# PCB_ALIM_version_5.net
KiCad netlist of a schematic drawn in EAGLE
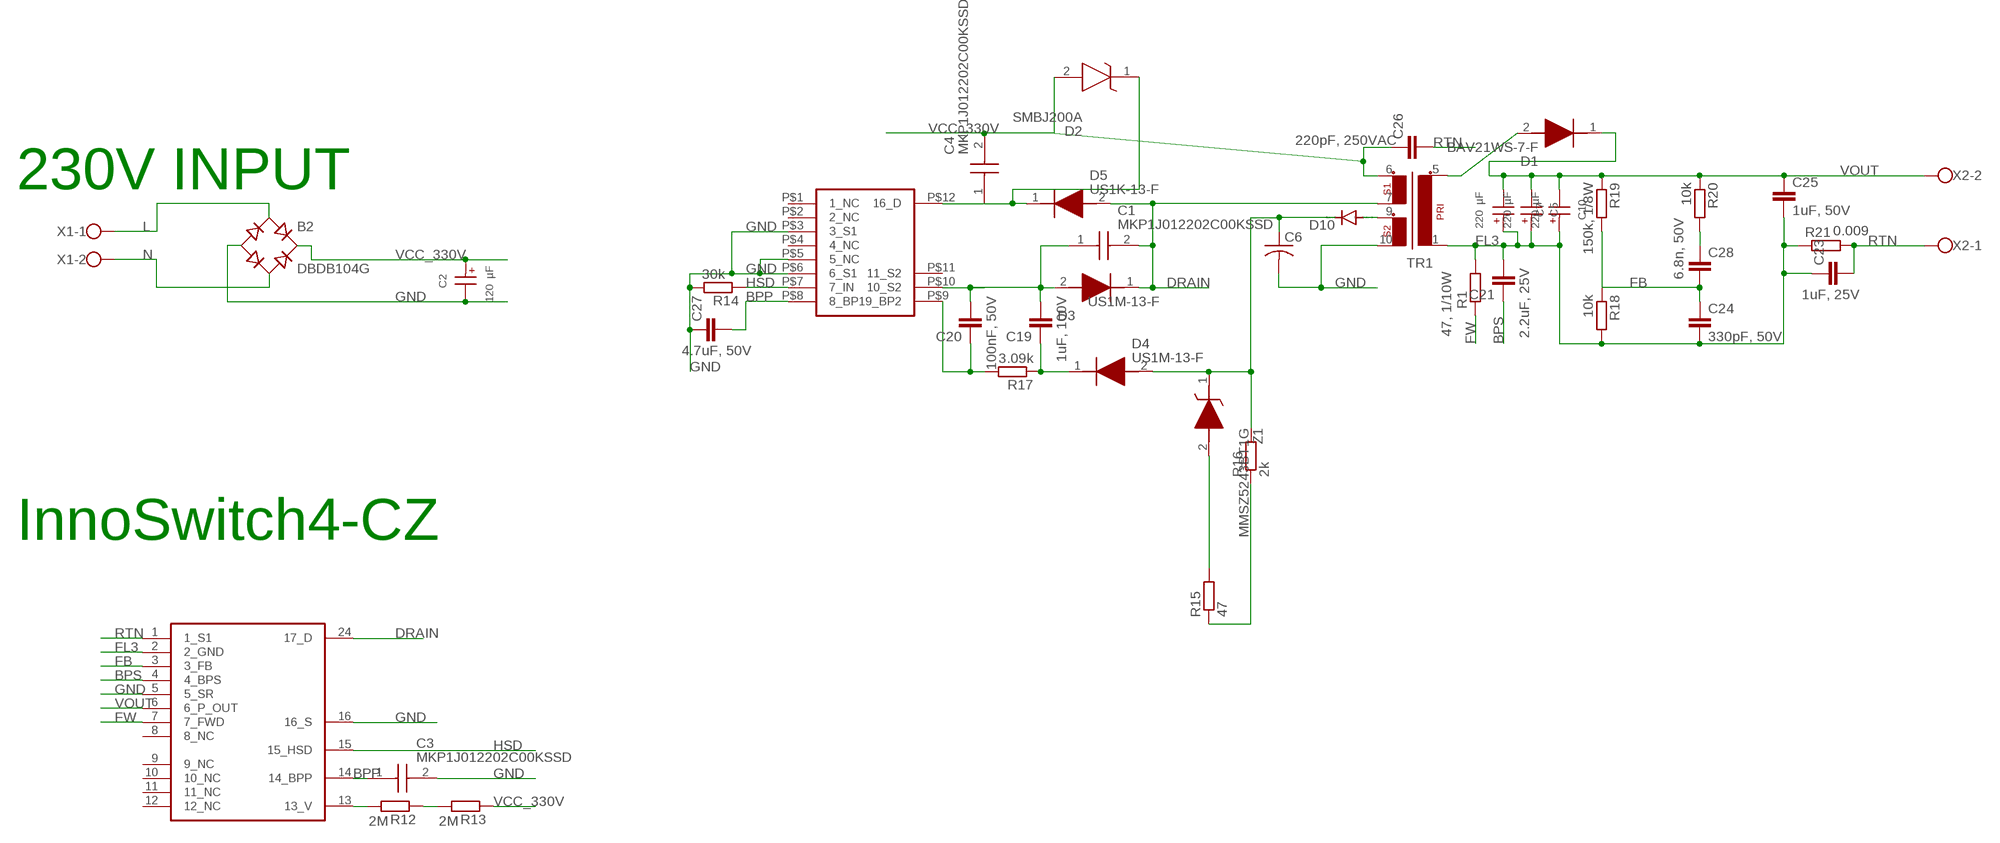
[diagram p0: schematic, sheet 1]

(export (version "E")
  (design (tool "Eeschema 10.0.6"))
  (components
    (comp (ref "B2")
      (value "DBDB104G")
      (footprint "eagle-import:DB")
      (libsource (lib "eagle-import") (part "DB?GDB104"))
    )
    (comp (ref "C1")
      (value "MKP1J012202C00KSSD")
      (footprint "eagle-import:MKP1J012202C00KSSD")
      (fields (field (name "MOUSER_PART_NUMBER") "505-M102200/630/10"))
      (libsource (lib "eagle-import") (part "MKP1J012202C00KSSD"))
    )
    (comp (ref "C2")
      (value "120 µF")
      (footprint "eagle-import:WCAP-ATG8_18X41X7.5(DXL)")
      (libsource (lib "eagle-import") (part "WCAP-ATG8_18X41_860011381013"))
    )
    (comp (ref "C3")
      (value "MKP1J012202C00KSSD")
      (footprint "eagle-import:MKP1J012202C00KSSD")
      (fields (field (name "MOUSER_PART_NUMBER") "505-M102200/630/10"))
      (libsource (lib "eagle-import") (part "MKP1J012202C00KSSD"))
    )
    (comp (ref "C4")
      (value "MKP1J012202C00KSSD")
      (footprint "eagle-import:MKP1J012202C00KSSD")
      (fields (field (name "MOUSER_PART_NUMBER") "505-M102200/630/10"))
      (libsource (lib "eagle-import") (part "MKP1J012202C00KSSD"))
    )
    (comp (ref "C5")
      (value "220 µF")
      (footprint "eagle-import:WCAP-ASLI_10X10.5(DXL)")
      (libsource (lib "eagle-import") (part "WCAP-ASLI_10X10.5_865080657018"))
    )
    (comp (ref "C6")
      (value "C-US050H075X075")
      (footprint "eagle-import:C050H075X075")
      (libsource (lib "eagle-import") (part "C-US050H075X075"))
    )
    (comp (ref "C7")
      (value "220 µF")
      (footprint "eagle-import:WCAP-ASLI_10X10.5(DXL)")
      (libsource (lib "eagle-import") (part "WCAP-ASLI_10X10.5_865080657018"))
    )
    (comp (ref "C10")
      (value "220 µF")
      (footprint "eagle-import:WCAP-ASLI_10X10.5(DXL)")
      (libsource (lib "eagle-import") (part "WCAP-ASLI_10X10.5_865080657018"))
    )
    (comp (ref "C19")
      (value "1uF, 100V")
      (footprint "eagle-import:C0603")
      (libsource (lib "eagle-import") (part "C-EUC0603"))
    )
    (comp (ref "C20")
      (value "100nF, 50V")
      (footprint "eagle-import:C0603")
      (libsource (lib "eagle-import") (part "C-EUC0603"))
    )
    (comp (ref "C21")
      (value "2.2uF, 25V")
      (footprint "eagle-import:C0603")
      (libsource (lib "eagle-import") (part "C-EUC0603"))
    )
    (comp (ref "C23")
      (value "1uF, 25V")
      (footprint "eagle-import:C0603")
      (libsource (lib "eagle-import") (part "C-EUC0603"))
    )
    (comp (ref "C24")
      (value "330pF, 50V")
      (footprint "eagle-import:C0603")
      (libsource (lib "eagle-import") (part "C-EUC0603"))
    )
    (comp (ref "C25")
      (value "1uF, 50V")
      (footprint "eagle-import:C0603")
      (libsource (lib "eagle-import") (part "C-EUC0603"))
    )
    (comp (ref "C26")
      (value "220pF, 250VAC")
      (footprint "eagle-import:C0603")
      (libsource (lib "eagle-import") (part "C-EUC0603"))
    )
    (comp (ref "C27")
      (value "4.7uF, 50V")
      (footprint "eagle-import:C0603")
      (libsource (lib "eagle-import") (part "C-EUC0603"))
    )
    (comp (ref "C28")
      (value "6.8n, 50V")
      (footprint "eagle-import:C0603")
      (libsource (lib "eagle-import") (part "C-EUC0603"))
    )
    (comp (ref "D1")
      (value "BAV21WS-7-F")
      (footprint "eagle-import:SOD2513X120N")
      (fields (field (name "MOUSER_PART_NUMBER") "621-BAV21WS-F"))
      (libsource (lib "eagle-import") (part "BAV21WS-7-F"))
    )
    (comp (ref "D2")
      (value "SMBJ200A")
      (footprint "eagle-import:DIOM5436X261N")
      (fields (field (name "MOUSER_PART_NUMBER") "576-SMBJ200A"))
      (libsource (lib "eagle-import") (part "SMBJ200A"))
    )
    (comp (ref "D3")
      (value "US1M-13-F")
      (footprint "eagle-import:SODFL5226X240N")
      (fields (field (name "MOUSER_PART_NUMBER") "621-US1M-F"))
      (libsource (lib "eagle-import") (part "US1M-13-F"))
    )
    (comp (ref "D4")
      (value "US1M-13-F")
      (footprint "eagle-import:SODFL5226X240N")
      (fields (field (name "MOUSER_PART_NUMBER") "621-US1M-F"))
      (libsource (lib "eagle-import") (part "US1M-13-F"))
    )
    (comp (ref "D5")
      (value "US1K-13-F")
      (footprint "eagle-import:DIOM5226X240N")
      (fields (field (name "MOUSER_PART_NUMBER") "621-US1K-F"))
      (libsource (lib "eagle-import") (part "US1K-13-F"))
    )
    (comp (ref "D10")
      (value "1N4933")
      (footprint "eagle-import:DO41-10")
      (libsource (lib "eagle-import") (part "1N4933"))
    )
    (comp (ref "R1")
      (value "47, 1/10W")
      (footprint "eagle-import:R0603")
      (libsource (lib "eagle-import") (part "R-EU_R0603"))
    )
    (comp (ref "R12")
      (value "2M")
      (footprint "eagle-import:R0603")
      (libsource (lib "eagle-import") (part "R-EU_R0603"))
    )
    (comp (ref "R13")
      (value "2M")
      (footprint "eagle-import:R0603")
      (libsource (lib "eagle-import") (part "R-EU_R0603"))
    )
    (comp (ref "R14")
      (value "30k")
      (footprint "eagle-import:R0603")
      (libsource (lib "eagle-import") (part "R-EU_R0603"))
    )
    (comp (ref "R15")
      (value "47")
      (footprint "eagle-import:R0603")
      (libsource (lib "eagle-import") (part "R-EU_R0603"))
    )
    (comp (ref "R16")
      (value "2k")
      (footprint "eagle-import:R0603")
      (libsource (lib "eagle-import") (part "R-EU_R0603"))
    )
    (comp (ref "R17")
      (value "3.09k")
      (footprint "eagle-import:R0603")
      (libsource (lib "eagle-import") (part "R-EU_R0603"))
    )
    (comp (ref "R18")
      (value "10k")
      (footprint "eagle-import:R0603")
      (libsource (lib "eagle-import") (part "R-EU_R0603"))
    )
    (comp (ref "R19")
      (value "150k, 1/8W")
      (footprint "eagle-import:R0603")
      (libsource (lib "eagle-import") (part "R-EU_R0603"))
    )
    (comp (ref "R20")
      (value "10k")
      (footprint "eagle-import:R0603")
      (libsource (lib "eagle-import") (part "R-EU_R0603"))
    )
    (comp (ref "R21")
      (value "0.009")
      (footprint "eagle-import:R0603")
      (libsource (lib "eagle-import") (part "R-EU_R0603"))
    )
    (comp (ref "TR1")
      (value "EI30-2")
      (footprint "eagle-import:EI30-2")
      (libsource (lib "eagle-import") (part "EI30-2"))
    )
    (comp (ref "U$1")
      (value "INNOSWITCH4_DEVICE")
      (footprint "eagle-import:INNOSWITCH4_FOOTPRINT")
      (libsource (lib "eagle-import") (part "INNOSWITCH4_DEVICE"))
    )
    (comp (ref "U$2")
      (value "CPZ1061M_DEVICE")
      (footprint "eagle-import:CPZ1061M_FOOTPRINT")
      (libsource (lib "eagle-import") (part "CPZ1061M_DEVICE"))
    )
    (comp (ref "X1")
      (value "W237-102")
      (footprint "eagle-import:W237-102")
      (fields (field (name "MPN") "237-102"))
      (libsource (lib "eagle-import") (part "W237-102"))
    )
    (comp (ref "X2")
      (value "W237-102")
      (footprint "eagle-import:W237-102")
      (fields (field (name "MPN") "237-102"))
      (libsource (lib "eagle-import") (part "W237-102"))
    )
    (comp (ref "Z1")
      (value "MMSZ5243BT1G")
      (footprint "eagle-import:SOD3716X135N")
      (fields (field (name "MOUSER_PART_NUMBER") "863-MMSZ5243BT1G"))
      (libsource (lib "eagle-import") (part "MMSZ5243BT1G"))
    )
  )
  (nets
    (net (code "1") (name "/BPP") (class "Default")
      (node (ref "C27") (pin "2") (pinfunction "2_2") (pintype "passive"))
      (node (ref "C3") (pin "1") (pinfunction "1_1") (pintype "bidirectional"))
      (node (ref "U$1") (pin "14") (pinfunction "14_BPP_14") (pintype "output"))
      (node (ref "U$2") (pin "P$8") (pinfunction "8_BP1_P$8") (pintype "input"))
    )
    (net (code "2") (name "/BPS") (class "Default")
      (node (ref "C21") (pin "1") (pinfunction "1_1") (pintype "passive"))
      (node (ref "U$1") (pin "4") (pinfunction "4_BPS_4") (pintype "input"))
    )
    (net (code "3") (name "/DRAIN") (class "Default")
      (node (ref "C1") (pin "2") (pinfunction "2_2") (pintype "bidirectional"))
      (node (ref "D3") (pin "1") (pinfunction "K_1") (pintype "bidirectional"))
      (node (ref "D5") (pin "2") (pinfunction "A_2") (pintype "bidirectional"))
      (node (ref "TR1") (pin "7") (pinfunction "4_7") (pintype "passive"))
      (node (ref "U$1") (pin "24") (pinfunction "17_D_24") (pintype "output"))
    )
    (net (code "4") (name "/FB") (class "Default")
      (node (ref "C24") (pin "1") (pinfunction "1_1") (pintype "passive"))
      (node (ref "C28") (pin "2") (pinfunction "2_2") (pintype "passive"))
      (node (ref "R18") (pin "1") (pinfunction "1_1") (pintype "passive"))
      (node (ref "R19") (pin "2") (pinfunction "2_2") (pintype "passive"))
      (node (ref "U$1") (pin "3") (pinfunction "3_FB_3") (pintype "input"))
    )
    (net (code "5") (name "/FL3") (class "Default")
      (node (ref "C10") (pin "1") (pinfunction "+_1") (pintype "passive"))
      (node (ref "C21") (pin "2") (pinfunction "2_2") (pintype "passive"))
      (node (ref "C23") (pin "1") (pinfunction "1_1") (pintype "passive"))
      (node (ref "C24") (pin "2") (pinfunction "2_2") (pintype "passive"))
      (node (ref "C25") (pin "2") (pinfunction "2_2") (pintype "passive"))
      (node (ref "C5") (pin "1") (pinfunction "+_1") (pintype "passive"))
      (node (ref "C7") (pin "1") (pinfunction "+_1") (pintype "passive"))
      (node (ref "R1") (pin "2") (pinfunction "2_2") (pintype "passive"))
      (node (ref "R18") (pin "2") (pinfunction "2_2") (pintype "passive"))
      (node (ref "R21") (pin "1") (pinfunction "1_1") (pintype "passive"))
      (node (ref "TR1") (pin "1") (pinfunction "1_1") (pintype "passive"))
      (node (ref "U$1") (pin "2") (pinfunction "2_GND_2") (pintype "input"))
    )
    (net (code "6") (name "/FW") (class "Default")
      (node (ref "R1") (pin "1") (pinfunction "1_1") (pintype "passive"))
      (node (ref "U$1") (pin "7") (pinfunction "7_FWD_7") (pintype "input"))
    )
    (net (code "7") (name "/GND") (class "Default")
      (node (ref "B2") (pin "-") (pinfunction "-_-") (pintype "passive"))
      (node (ref "C2") (pin "2") (pinfunction "-_2") (pintype "passive"))
      (node (ref "C27") (pin "1") (pinfunction "1_1") (pintype "passive"))
      (node (ref "C3") (pin "2") (pinfunction "2_2") (pintype "bidirectional"))
      (node (ref "C6") (pin "2") (pinfunction "2_2") (pintype "passive"))
      (node (ref "R14") (pin "2") (pinfunction "2_2") (pintype "passive"))
      (node (ref "TR1") (pin "10") (pinfunction "6_10") (pintype "passive"))
      (node (ref "U$1") (pin "16") (pinfunction "16_S_16") (pintype "output"))
      (node (ref "U$1") (pin "5") (pinfunction "5_SR_5") (pintype "input"))
      (node (ref "U$2") (pin "P$3") (pinfunction "3_S1_P$3") (pintype "input"))
      (node (ref "U$2") (pin "P$5") (pinfunction "5_NC_P$5") (pintype "input"))
      (node (ref "U$2") (pin "P$6") (pinfunction "6_S1_P$6") (pintype "input"))
    )
    (net (code "8") (name "/HSD") (class "Default")
      (node (ref "R14") (pin "1") (pinfunction "1_1") (pintype "passive"))
      (node (ref "U$1") (pin "15") (pinfunction "15_HSD_15") (pintype "output"))
      (node (ref "U$2") (pin "P$7") (pinfunction "7_IN_P$7") (pintype "input"))
    )
    (net (code "9") (name "/L") (class "Default")
      (node (ref "B2") (pin "AC1") (pinfunction "AC1_AC1") (pintype "passive"))
      (node (ref "X1") (pin "1") (pinfunction "KL_1") (pintype "passive"))
    )
    (net (code "10") (name "/N") (class "Default")
      (node (ref "B2") (pin "AC2") (pinfunction "AC2_AC2") (pintype "passive"))
      (node (ref "X1") (pin "2") (pinfunction "KL_2") (pintype "passive"))
    )
    (net (code "11") (name "/RTN") (class "Default")
      (node (ref "C23") (pin "2") (pinfunction "2_2") (pintype "passive"))
      (node (ref "C26") (pin "2") (pinfunction "2_2") (pintype "passive"))
      (node (ref "R21") (pin "2") (pinfunction "2_2") (pintype "passive"))
      (node (ref "U$1") (pin "1") (pinfunction "1_S1_1") (pintype "input"))
      (node (ref "X2") (pin "1") (pinfunction "KL_1") (pintype "passive"))
    )
    (net (code "12") (name "/VCC_330V") (class "Default")
      (node (ref "B2") (pin "+") (pinfunction "+_+") (pintype "passive"))
      (node (ref "C2") (pin "1") (pinfunction "+_1") (pintype "passive"))
      (node (ref "C26") (pin "1") (pinfunction "1_1") (pintype "passive"))
      (node (ref "C4") (pin "2") (pinfunction "2_2") (pintype "bidirectional"))
      (node (ref "D2") (pin "2") (pinfunction "A_2") (pintype "bidirectional"))
      (node (ref "R13") (pin "1") (pinfunction "1_1") (pintype "passive"))
      (node (ref "TR1") (pin "6") (pinfunction "3_6") (pintype "passive"))
    )
    (net (code "13") (name "/VOUT") (class "Default")
      (node (ref "C10") (pin "2") (pinfunction "-_2") (pintype "passive"))
      (node (ref "C25") (pin "1") (pinfunction "1_1") (pintype "passive"))
      (node (ref "C5") (pin "2") (pinfunction "-_2") (pintype "passive"))
      (node (ref "C7") (pin "2") (pinfunction "-_2") (pintype "passive"))
      (node (ref "D1") (pin "1") (pinfunction "K_1") (pintype "bidirectional"))
      (node (ref "R19") (pin "1") (pinfunction "1_1") (pintype "passive"))
      (node (ref "R20") (pin "1") (pinfunction "1_1") (pintype "passive"))
      (node (ref "U$1") (pin "6") (pinfunction "6_P_OUT_6") (pintype "input"))
      (node (ref "X2") (pin "2") (pinfunction "KL_2") (pintype "passive"))
    )
    (net (code "14") (name "Net-(C28-Pad1)") (class "Default")
      (node (ref "C28") (pin "1") (pinfunction "1_1") (pintype "passive"))
      (node (ref "R20") (pin "2") (pinfunction "2_2") (pintype "passive"))
    )
    (net (code "15") (name "Net-(D1-A)") (class "Default")
      (node (ref "D1") (pin "2") (pinfunction "A_2") (pintype "bidirectional"))
      (node (ref "TR1") (pin "5") (pinfunction "2_5") (pintype "passive"))
    )
    (net (code "16") (name "Net-(D2-K)") (class "Default")
      (node (ref "C4") (pin "1") (pinfunction "1_1") (pintype "bidirectional"))
      (node (ref "D2") (pin "1") (pinfunction "K_1") (pintype "bidirectional"))
      (node (ref "D5") (pin "1") (pinfunction "K_1") (pintype "bidirectional"))
      (node (ref "U$2") (pin "P$12") (pinfunction "16_D_P$12") (pintype "tri_state"))
    )
    (net (code "17") (name "Net-(D3-A)") (class "Default")
      (node (ref "C1") (pin "1") (pinfunction "1_1") (pintype "bidirectional"))
      (node (ref "C19") (pin "2") (pinfunction "2_2") (pintype "passive"))
      (node (ref "C20") (pin "2") (pinfunction "2_2") (pintype "passive"))
      (node (ref "D3") (pin "2") (pinfunction "A_2") (pintype "bidirectional"))
      (node (ref "U$2") (pin "P$10") (pinfunction "10_S2_P$10") (pintype "tri_state"))
    )
    (net (code "18") (name "Net-(D4-A)") (class "Default")
      (node (ref "C6") (pin "1") (pinfunction "1_1") (pintype "passive"))
      (node (ref "D10") (pin "C") (pinfunction "C_C") (pintype "passive"))
      (node (ref "D4") (pin "2") (pinfunction "A_2") (pintype "bidirectional"))
      (node (ref "R16") (pin "2") (pinfunction "2_2") (pintype "passive"))
      (node (ref "Z1") (pin "1") (pinfunction "K_1") (pintype "bidirectional"))
    )
    (net (code "19") (name "Net-(D4-K)") (class "Default")
      (node (ref "C19") (pin "1") (pinfunction "1_1") (pintype "passive"))
      (node (ref "D4") (pin "1") (pinfunction "K_1") (pintype "bidirectional"))
      (node (ref "R17") (pin "1") (pinfunction "1_1") (pintype "passive"))
    )
    (net (code "20") (name "Net-(R12-Pad1)") (class "Default")
      (node (ref "R12") (pin "1") (pinfunction "1_1") (pintype "passive"))
      (node (ref "R13") (pin "2") (pinfunction "2_2") (pintype "passive"))
    )
    (net (code "21") (name "Net-(R15-Pad1)") (class "Default")
      (node (ref "R15") (pin "1") (pinfunction "1_1") (pintype "passive"))
      (node (ref "R16") (pin "1") (pinfunction "1_1") (pintype "passive"))
    )
    (net (code "22") (name "Net-(TR1-5)") (class "Default")
      (node (ref "D10") (pin "A") (pinfunction "A_A") (pintype "passive"))
      (node (ref "TR1") (pin "9") (pinfunction "5_9") (pintype "passive"))
    )
    (net (code "23") (name "Net-(U$1-13_V)") (class "Default")
      (node (ref "R12") (pin "2") (pinfunction "2_2") (pintype "passive"))
      (node (ref "U$1") (pin "13") (pinfunction "13_V_13") (pintype "output"))
    )
    (net (code "24") (name "Net-(U$2-9_BP2)") (class "Default")
      (node (ref "C20") (pin "1") (pinfunction "1_1") (pintype "passive"))
      (node (ref "R17") (pin "2") (pinfunction "2_2") (pintype "passive"))
      (node (ref "U$2") (pin "P$9") (pinfunction "9_BP2_P$9") (pintype "tri_state"))
    )
    (net (code "25") (name "Net-(Z1-A)") (class "Default")
      (node (ref "R15") (pin "2") (pinfunction "2_2") (pintype "passive"))
      (node (ref "Z1") (pin "2") (pinfunction "A_2") (pintype "bidirectional"))
    )
    (net (code "26") (name "unconnected-(U$1-8_NC-Pad8)") (class "Default")
      (node (ref "U$1") (pin "8") (pinfunction "8_NC_8") (pintype "input"))
    )
    (net (code "27") (name "unconnected-(U$1-9_NC-Pad9)") (class "Default")
      (node (ref "U$1") (pin "9") (pinfunction "9_NC_9") (pintype "input"))
    )
    (net (code "28") (name "unconnected-(U$1-10_NC-Pad10)") (class "Default")
      (node (ref "U$1") (pin "10") (pinfunction "10_NC_10") (pintype "input"))
    )
    (net (code "29") (name "unconnected-(U$1-11_NC-Pad11)") (class "Default")
      (node (ref "U$1") (pin "11") (pinfunction "11_NC_11") (pintype "input"))
    )
    (net (code "30") (name "unconnected-(U$1-12_NC-Pad12)") (class "Default")
      (node (ref "U$1") (pin "12") (pinfunction "12_NC_12") (pintype "input"))
    )
    (net (code "31") (name "unconnected-(U$2-1_NC-PadP$1)") (class "Default")
      (node (ref "U$2") (pin "P$1") (pinfunction "1_NC_P$1") (pintype "input"))
    )
    (net (code "32") (name "unconnected-(U$2-2_NC-PadP$2)") (class "Default")
      (node (ref "U$2") (pin "P$2") (pinfunction "2_NC_P$2") (pintype "input"))
    )
    (net (code "33") (name "unconnected-(U$2-4_NC-PadP$4)") (class "Default")
      (node (ref "U$2") (pin "P$4") (pinfunction "4_NC_P$4") (pintype "input"))
    )
    (net (code "34") (name "unconnected-(U$2-11_S2-PadP$11)") (class "Default")
      (node (ref "U$2") (pin "P$11") (pinfunction "11_S2_P$11") (pintype "tri_state"))
    )
  )
)
